# 6thNov_submission_12V_everywhere.net
KiCad netlist of a schematic drawn in EAGLE
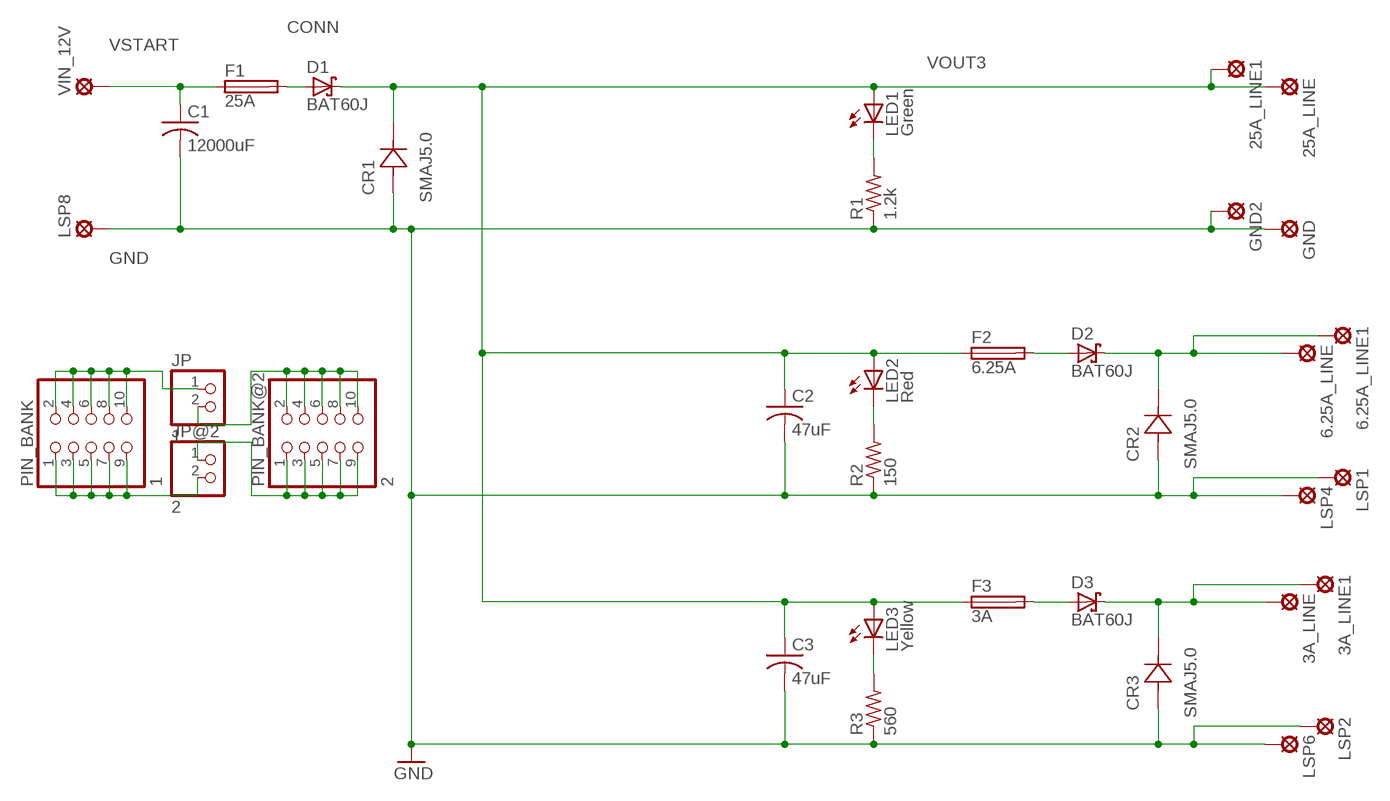
[diagram p0: schematic, sheet 1]

(export (version "E")
  (design (tool "Eeschema 10.0.6"))
  (components
    (comp (ref "3A_LINE")
      (value "SE13")
      (footprint "eagle-import:SE13")
      (libsource (lib "eagle-import") (part "SE13"))
    )
    (comp (ref "3A_LINE1")
      (value "SE13")
      (footprint "eagle-import:SE13")
      (libsource (lib "eagle-import") (part "SE13"))
    )
    (comp (ref "6.25A_LINE")
      (value "SE13")
      (footprint "eagle-import:SE13")
      (libsource (lib "eagle-import") (part "SE13"))
    )
    (comp (ref "6.25A_LINE1")
      (value "SE13")
      (footprint "eagle-import:SE13")
      (libsource (lib "eagle-import") (part "SE13"))
    )
    (comp (ref "25A_LINE")
      (value "SE13")
      (footprint "eagle-import:SE13")
      (libsource (lib "eagle-import") (part "SE13"))
    )
    (comp (ref "25A_LINE1")
      (value "SE13")
      (footprint "eagle-import:SE13")
      (libsource (lib "eagle-import") (part "SE13"))
    )
    (comp (ref "C1")
      (value "12000uF")
      (footprint "eagle-import:C1206K")
      (libsource (lib "eagle-import") (part "C-USC1206K"))
    )
    (comp (ref "C2")
      (value "47uF")
      (footprint "eagle-import:C1206K")
      (libsource (lib "eagle-import") (part "C-USC1206K"))
    )
    (comp (ref "C3")
      (value "47uF")
      (footprint "eagle-import:C1206K")
      (libsource (lib "eagle-import") (part "C-USC1206K"))
    )
    (comp (ref "CR1")
      (value "SMAJ5.0")
      (footprint "eagle-import:SMASERIES")
      (libsource (lib "eagle-import") (part "SMAJ5.0"))
    )
    (comp (ref "CR2")
      (value "SMAJ5.0")
      (footprint "eagle-import:SMASERIES")
      (libsource (lib "eagle-import") (part "SMAJ5.0"))
    )
    (comp (ref "CR3")
      (value "SMAJ5.0")
      (footprint "eagle-import:SMASERIES")
      (libsource (lib "eagle-import") (part "SMAJ5.0"))
    )
    (comp (ref "D1")
      (value "BAT60J")
      (footprint "eagle-import:SOD323_ST")
      (libsource (lib "eagle-import") (part "BAT60J"))
    )
    (comp (ref "D2")
      (value "BAT60J")
      (footprint "eagle-import:SOD323_ST")
      (libsource (lib "eagle-import") (part "BAT60J"))
    )
    (comp (ref "D3")
      (value "BAT60J")
      (footprint "eagle-import:SOD323_ST")
      (libsource (lib "eagle-import") (part "BAT60J"))
    )
    (comp (ref "F1")
      (value "25A")
      (footprint "eagle-import:TE5")
      (libsource (lib "eagle-import") (part "TE5"))
    )
    (comp (ref "F2")
      (value "6.25A")
      (footprint "eagle-import:TE5")
      (libsource (lib "eagle-import") (part "TE5"))
    )
    (comp (ref "F3")
      (value "3A")
      (footprint "eagle-import:TE5")
      (libsource (lib "eagle-import") (part "TE5"))
    )
    (comp (ref "GND")
      (value "SE13")
      (footprint "eagle-import:SE13")
      (libsource (lib "eagle-import") (part "SE13"))
    )
    (comp (ref "GND2")
      (value "SE13")
      (footprint "eagle-import:SE13")
      (libsource (lib "eagle-import") (part "SE13"))
    )
    (comp (ref "JP")
      (value "1")
      (footprint "eagle-import:1X02")
      (libsource (lib "eagle-import") (part "PINHD-1X2"))
    )
    (comp (ref "JP@2")
      (value "2")
      (footprint "eagle-import:1X02")
      (libsource (lib "eagle-import") (part "PINHD-1X2"))
    )
    (comp (ref "LED1")
      (value "Green")
      (footprint "eagle-import:CHIPLED_1206")
      (libsource (lib "eagle-import") (part "LEDCHIPLED_1206"))
    )
    (comp (ref "LED2")
      (value "Red")
      (footprint "eagle-import:CHIPLED_1206")
      (libsource (lib "eagle-import") (part "LEDCHIPLED_1206"))
    )
    (comp (ref "LED3")
      (value "Yellow")
      (footprint "eagle-import:CHIPLED_1206")
      (libsource (lib "eagle-import") (part "LEDCHIPLED_1206"))
    )
    (comp (ref "LSP1")
      (value "SE13")
      (footprint "eagle-import:SE13")
      (libsource (lib "eagle-import") (part "SE13"))
    )
    (comp (ref "LSP2")
      (value "SE13")
      (footprint "eagle-import:SE13")
      (libsource (lib "eagle-import") (part "SE13"))
    )
    (comp (ref "LSP4")
      (value "SE13")
      (footprint "eagle-import:SE13")
      (libsource (lib "eagle-import") (part "SE13"))
    )
    (comp (ref "LSP6")
      (value "SE13")
      (footprint "eagle-import:SE13")
      (libsource (lib "eagle-import") (part "SE13"))
    )
    (comp (ref "LSP8")
      (value "SE13")
      (footprint "eagle-import:SE13")
      (libsource (lib "eagle-import") (part "SE13"))
    )
    (comp (ref "PIN_BANK")
      (value "1")
      (footprint "eagle-import:2X05")
      (libsource (lib "eagle-import") (part "PINHD-2X5"))
    )
    (comp (ref "PIN_BANK@2")
      (value "2")
      (footprint "eagle-import:2X05")
      (libsource (lib "eagle-import") (part "PINHD-2X5"))
    )
    (comp (ref "R1")
      (value "1.2k")
      (footprint "eagle-import:R1206")
      (libsource (lib "eagle-import") (part "R-US_R1206"))
    )
    (comp (ref "R2")
      (value "150")
      (footprint "eagle-import:R1206")
      (libsource (lib "eagle-import") (part "R-US_R1206"))
    )
    (comp (ref "R3")
      (value "560")
      (footprint "eagle-import:R1206")
      (libsource (lib "eagle-import") (part "R-US_R1206"))
    )
    (comp (ref "VIN_12V")
      (value "SE13")
      (footprint "eagle-import:SE13")
      (libsource (lib "eagle-import") (part "SE13"))
    )
  )
  (nets
    (net (code "1") (name "/CONN") (class "Default")
      (node (ref "D1") (pin "A") (pinfunction "A_A") (pintype "passive"))
      (node (ref "F1") (pin "2") (pinfunction "2_2") (pintype "passive"))
    )
    (net (code "2") (name "/VOUT3") (class "Default")
      (node (ref "25A_LINE") (pin "MP") (pinfunction "MP_MP") (pintype "passive"))
      (node (ref "25A_LINE1") (pin "MP") (pinfunction "MP_MP") (pintype "passive"))
      (node (ref "C2") (pin "1") (pinfunction "1_1") (pintype "passive"))
      (node (ref "C3") (pin "1") (pinfunction "1_1") (pintype "passive"))
      (node (ref "CR1") (pin "1") (pinfunction "2_1") (pintype "passive"))
      (node (ref "D1") (pin "C") (pinfunction "C_C") (pintype "passive"))
      (node (ref "F2") (pin "1") (pinfunction "1_1") (pintype "passive"))
      (node (ref "F3") (pin "1") (pinfunction "1_1") (pintype "passive"))
      (node (ref "LED1") (pin "A") (pinfunction "A_A") (pintype "passive"))
      (node (ref "LED2") (pin "A") (pinfunction "A_A") (pintype "passive"))
      (node (ref "LED3") (pin "A") (pinfunction "A_A") (pintype "passive"))
    )
    (net (code "3") (name "/VSTART") (class "Default")
      (node (ref "C1") (pin "1") (pinfunction "1_1") (pintype "passive"))
      (node (ref "F1") (pin "1") (pinfunction "1_1") (pintype "passive"))
      (node (ref "VIN_12V") (pin "MP") (pinfunction "MP_MP") (pintype "passive"))
    )
    (net (code "4") (name "GND") (class "Default")
      (node (ref "C1") (pin "2") (pinfunction "2_2") (pintype "passive"))
      (node (ref "C2") (pin "2") (pinfunction "2_2") (pintype "passive"))
      (node (ref "C3") (pin "2") (pinfunction "2_2") (pintype "passive"))
      (node (ref "CR1") (pin "2") (pinfunction "1_2") (pintype "passive"))
      (node (ref "CR2") (pin "2") (pinfunction "1_2") (pintype "passive"))
      (node (ref "CR3") (pin "2") (pinfunction "1_2") (pintype "passive"))
      (node (ref "GND") (pin "MP") (pinfunction "MP_MP") (pintype "passive"))
      (node (ref "GND2") (pin "MP") (pinfunction "MP_MP") (pintype "passive"))
      (node (ref "LSP1") (pin "MP") (pinfunction "MP_MP") (pintype "passive"))
      (node (ref "LSP2") (pin "MP") (pinfunction "MP_MP") (pintype "passive"))
      (node (ref "LSP4") (pin "MP") (pinfunction "MP_MP") (pintype "passive"))
      (node (ref "LSP6") (pin "MP") (pinfunction "MP_MP") (pintype "passive"))
      (node (ref "LSP8") (pin "MP") (pinfunction "MP_MP") (pintype "passive"))
      (node (ref "R1") (pin "1") (pinfunction "1_1") (pintype "passive"))
      (node (ref "R2") (pin "1") (pinfunction "1_1") (pintype "passive"))
      (node (ref "R3") (pin "1") (pinfunction "1_1") (pintype "passive"))
    )
    (net (code "5") (name "Net-(CR2-2)") (class "Default")
      (node (ref "6.25A_LINE") (pin "MP") (pinfunction "MP_MP") (pintype "passive"))
      (node (ref "6.25A_LINE1") (pin "MP") (pinfunction "MP_MP") (pintype "passive"))
      (node (ref "CR2") (pin "1") (pinfunction "2_1") (pintype "passive"))
      (node (ref "D2") (pin "C") (pinfunction "C_C") (pintype "passive"))
    )
    (net (code "6") (name "Net-(CR3-2)") (class "Default")
      (node (ref "3A_LINE") (pin "MP") (pinfunction "MP_MP") (pintype "passive"))
      (node (ref "3A_LINE1") (pin "MP") (pinfunction "MP_MP") (pintype "passive"))
      (node (ref "CR3") (pin "1") (pinfunction "2_1") (pintype "passive"))
      (node (ref "D3") (pin "C") (pinfunction "C_C") (pintype "passive"))
    )
    (net (code "7") (name "Net-(D2-PadA)") (class "Default")
      (node (ref "D2") (pin "A") (pinfunction "A_A") (pintype "passive"))
      (node (ref "F2") (pin "2") (pinfunction "2_2") (pintype "passive"))
    )
    (net (code "8") (name "Net-(D3-PadA)") (class "Default")
      (node (ref "D3") (pin "A") (pinfunction "A_A") (pintype "passive"))
      (node (ref "F3") (pin "2") (pinfunction "2_2") (pintype "passive"))
    )
    (net (code "9") (name "Net-(JP-Pad1)") (class "Default")
      (node (ref "JP") (pin "1") (pinfunction "1_1") (pintype "passive"))
      (node (ref "PIN_BANK") (pin "10") (pinfunction "10_10") (pintype "passive"))
      (node (ref "PIN_BANK") (pin "2") (pinfunction "2_2") (pintype "passive"))
      (node (ref "PIN_BANK") (pin "4") (pinfunction "4_4") (pintype "passive"))
      (node (ref "PIN_BANK") (pin "6") (pinfunction "6_6") (pintype "passive"))
      (node (ref "PIN_BANK") (pin "8") (pinfunction "8_8") (pintype "passive"))
    )
    (net (code "10") (name "Net-(JP-Pad2)") (class "Default")
      (node (ref "JP") (pin "2") (pinfunction "2_2") (pintype "passive"))
      (node (ref "PIN_BANK@2") (pin "10") (pinfunction "10_10") (pintype "passive"))
      (node (ref "PIN_BANK@2") (pin "2") (pinfunction "2_2") (pintype "passive"))
      (node (ref "PIN_BANK@2") (pin "4") (pinfunction "4_4") (pintype "passive"))
      (node (ref "PIN_BANK@2") (pin "6") (pinfunction "6_6") (pintype "passive"))
      (node (ref "PIN_BANK@2") (pin "8") (pinfunction "8_8") (pintype "passive"))
    )
    (net (code "11") (name "Net-(JP@2-Pad1)") (class "Default")
      (node (ref "JP@2") (pin "1") (pinfunction "1_1") (pintype "passive"))
      (node (ref "PIN_BANK@2") (pin "1") (pinfunction "1_1") (pintype "passive"))
      (node (ref "PIN_BANK@2") (pin "3") (pinfunction "3_3") (pintype "passive"))
      (node (ref "PIN_BANK@2") (pin "5") (pinfunction "5_5") (pintype "passive"))
      (node (ref "PIN_BANK@2") (pin "7") (pinfunction "7_7") (pintype "passive"))
      (node (ref "PIN_BANK@2") (pin "9") (pinfunction "9_9") (pintype "passive"))
    )
    (net (code "12") (name "Net-(JP@2-Pad2)") (class "Default")
      (node (ref "JP@2") (pin "2") (pinfunction "2_2") (pintype "passive"))
      (node (ref "PIN_BANK") (pin "1") (pinfunction "1_1") (pintype "passive"))
      (node (ref "PIN_BANK") (pin "3") (pinfunction "3_3") (pintype "passive"))
      (node (ref "PIN_BANK") (pin "5") (pinfunction "5_5") (pintype "passive"))
      (node (ref "PIN_BANK") (pin "7") (pinfunction "7_7") (pintype "passive"))
      (node (ref "PIN_BANK") (pin "9") (pinfunction "9_9") (pintype "passive"))
    )
    (net (code "13") (name "Net-(LED1-PadC)") (class "Default")
      (node (ref "LED1") (pin "C") (pinfunction "C_C") (pintype "passive"))
      (node (ref "R1") (pin "2") (pinfunction "2_2") (pintype "passive"))
    )
    (net (code "14") (name "Net-(LED2-PadC)") (class "Default")
      (node (ref "LED2") (pin "C") (pinfunction "C_C") (pintype "passive"))
      (node (ref "R2") (pin "2") (pinfunction "2_2") (pintype "passive"))
    )
    (net (code "15") (name "Net-(LED3-PadC)") (class "Default")
      (node (ref "LED3") (pin "C") (pinfunction "C_C") (pintype "passive"))
      (node (ref "R3") (pin "2") (pinfunction "2_2") (pintype "passive"))
    )
  )
)
